# compute_hub.net
KiCad netlist of a schematic drawn in EAGLE
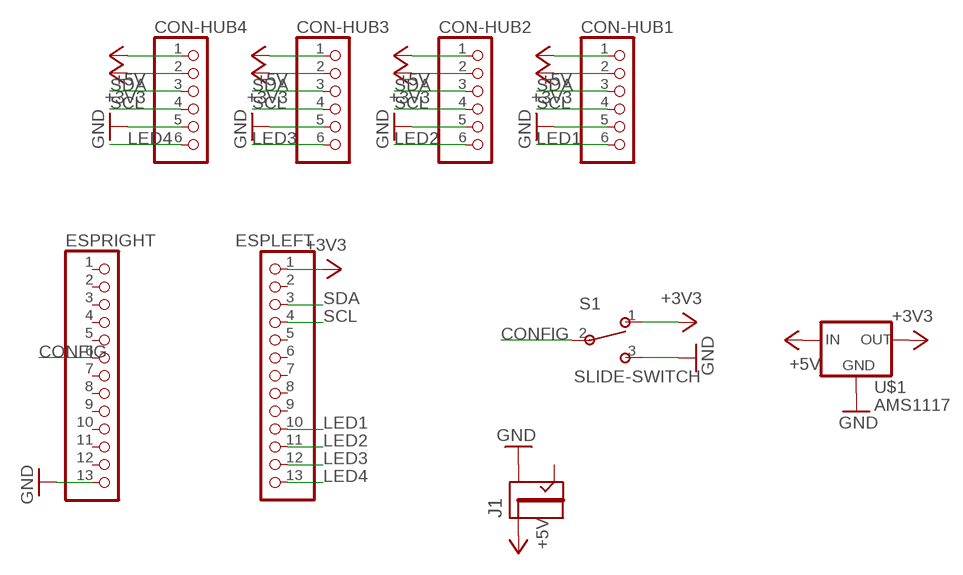
[diagram p0: schematic, sheet 1]

(export (version "E")
  (design (tool "Eeschema 10.0.6"))
  (components
    (comp (ref "CON-HUB1")
      (value "PINHD-1X6")
      (footprint "eagle-import:1X06")
      (libsource (lib "eagle-import") (part "PINHD-1X6"))
    )
    (comp (ref "CON-HUB2")
      (value "PINHD-1X6")
      (footprint "eagle-import:1X06")
      (libsource (lib "eagle-import") (part "PINHD-1X6"))
    )
    (comp (ref "CON-HUB3")
      (value "PINHD-1X6")
      (footprint "eagle-import:1X06")
      (libsource (lib "eagle-import") (part "PINHD-1X6"))
    )
    (comp (ref "CON-HUB4")
      (value "PINHD-1X6")
      (footprint "eagle-import:1X06")
      (libsource (lib "eagle-import") (part "PINHD-1X6"))
    )
    (comp (ref "ESPLEFT")
      (value "PINHD-1X13")
      (footprint "eagle-import:1X13")
      (libsource (lib "eagle-import") (part "PINHD-1X13"))
    )
    (comp (ref "ESPRIGHT")
      (value "PINHD-1X13")
      (footprint "eagle-import:1X13")
      (libsource (lib "eagle-import") (part "PINHD-1X13"))
    )
    (comp (ref "J1")
      (value "JACK2.1MM")
      (footprint "eagle-import:JACK_2.1MM")
      (libsource (lib "eagle-import") (part "JACK2.1MM"))
    )
    (comp (ref "S1")
      (value "SLIDE-SWITCH")
      (footprint "eagle-import:AYZ0102AGRLC")
      (libsource (lib "eagle-import") (part "SLIDE-SWITCH"))
    )
    (comp (ref "U$1")
      (value "AMS1117")
      (footprint "eagle-import:SOT223")
      (libsource (lib "eagle-import") (part "AMS1117"))
    )
  )
  (nets
    (net (code "1") (name "+3V3") (class "Default")
      (node (ref "CON-HUB1") (pin "2") (pinfunction "2_2") (pintype "passive"))
      (node (ref "CON-HUB2") (pin "2") (pinfunction "2_2") (pintype "passive"))
      (node (ref "CON-HUB3") (pin "2") (pinfunction "2_2") (pintype "passive"))
      (node (ref "CON-HUB4") (pin "2") (pinfunction "2_2") (pintype "passive"))
      (node (ref "ESPLEFT") (pin "1") (pinfunction "1_1") (pintype "passive"))
      (node (ref "S1") (pin "1") (pinfunction "1_1") (pintype "bidirectional"))
      (node (ref "U$1") (pin "2") (pinfunction "OUT_2") (pintype "passive"))
    )
    (net (code "2") (name "+5V") (class "Default")
      (node (ref "CON-HUB1") (pin "1") (pinfunction "1_1") (pintype "passive"))
      (node (ref "CON-HUB2") (pin "1") (pinfunction "1_1") (pintype "passive"))
      (node (ref "CON-HUB3") (pin "1") (pinfunction "1_1") (pintype "passive"))
      (node (ref "CON-HUB4") (pin "1") (pinfunction "1_1") (pintype "passive"))
      (node (ref "J1") (pin "PIN") (pinfunction "PIN_PIN") (pintype "bidirectional"))
      (node (ref "U$1") (pin "3") (pinfunction "IN_3") (pintype "input"))
    )
    (net (code "3") (name "/CONFIG") (class "Default")
      (node (ref "ESPRIGHT") (pin "6") (pinfunction "6_6") (pintype "passive"))
      (node (ref "S1") (pin "2") (pinfunction "2_2") (pintype "bidirectional"))
    )
    (net (code "4") (name "/LED1") (class "Default")
      (node (ref "CON-HUB1") (pin "6") (pinfunction "6_6") (pintype "passive"))
      (node (ref "ESPLEFT") (pin "10") (pinfunction "10_10") (pintype "passive"))
    )
    (net (code "5") (name "/LED2") (class "Default")
      (node (ref "CON-HUB2") (pin "6") (pinfunction "6_6") (pintype "passive"))
      (node (ref "ESPLEFT") (pin "11") (pinfunction "11_11") (pintype "passive"))
    )
    (net (code "6") (name "/LED3") (class "Default")
      (node (ref "CON-HUB3") (pin "6") (pinfunction "6_6") (pintype "passive"))
      (node (ref "ESPLEFT") (pin "12") (pinfunction "12_12") (pintype "passive"))
    )
    (net (code "7") (name "/LED4") (class "Default")
      (node (ref "CON-HUB4") (pin "6") (pinfunction "6_6") (pintype "passive"))
      (node (ref "ESPLEFT") (pin "13") (pinfunction "13_13") (pintype "passive"))
    )
    (net (code "8") (name "/SCL") (class "Default")
      (node (ref "CON-HUB1") (pin "4") (pinfunction "4_4") (pintype "passive"))
      (node (ref "CON-HUB2") (pin "4") (pinfunction "4_4") (pintype "passive"))
      (node (ref "CON-HUB3") (pin "4") (pinfunction "4_4") (pintype "passive"))
      (node (ref "CON-HUB4") (pin "4") (pinfunction "4_4") (pintype "passive"))
      (node (ref "ESPLEFT") (pin "4") (pinfunction "4_4") (pintype "passive"))
    )
    (net (code "9") (name "/SDA") (class "Default")
      (node (ref "CON-HUB1") (pin "3") (pinfunction "3_3") (pintype "passive"))
      (node (ref "CON-HUB2") (pin "3") (pinfunction "3_3") (pintype "passive"))
      (node (ref "CON-HUB3") (pin "3") (pinfunction "3_3") (pintype "passive"))
      (node (ref "CON-HUB4") (pin "3") (pinfunction "3_3") (pintype "passive"))
      (node (ref "ESPLEFT") (pin "3") (pinfunction "3_3") (pintype "passive"))
    )
    (net (code "10") (name "GND") (class "Default")
      (node (ref "CON-HUB1") (pin "5") (pinfunction "5_5") (pintype "passive"))
      (node (ref "CON-HUB2") (pin "5") (pinfunction "5_5") (pintype "passive"))
      (node (ref "CON-HUB3") (pin "5") (pinfunction "5_5") (pintype "passive"))
      (node (ref "CON-HUB4") (pin "5") (pinfunction "5_5") (pintype "passive"))
      (node (ref "ESPRIGHT") (pin "13") (pinfunction "13_13") (pintype "passive"))
      (node (ref "J1") (pin "SHUNT") (pinfunction "SHUNT_SHUNT") (pintype "bidirectional"))
      (node (ref "S1") (pin "3") (pinfunction "3_3") (pintype "bidirectional"))
      (node (ref "U$1") (pin "1") (pinfunction "GND_1") (pintype "input"))
    )
    (net (code "11") (name "unconnected-(ESPLEFT-Pad2)") (class "Default")
      (node (ref "ESPLEFT") (pin "2") (pinfunction "2_2") (pintype "passive"))
    )
    (net (code "12") (name "unconnected-(ESPLEFT-Pad5)") (class "Default")
      (node (ref "ESPLEFT") (pin "5") (pinfunction "5_5") (pintype "passive"))
    )
    (net (code "13") (name "unconnected-(ESPLEFT-Pad6)") (class "Default")
      (node (ref "ESPLEFT") (pin "6") (pinfunction "6_6") (pintype "passive"))
    )
    (net (code "14") (name "unconnected-(ESPLEFT-Pad7)") (class "Default")
      (node (ref "ESPLEFT") (pin "7") (pinfunction "7_7") (pintype "passive"))
    )
    (net (code "15") (name "unconnected-(ESPLEFT-Pad8)") (class "Default")
      (node (ref "ESPLEFT") (pin "8") (pinfunction "8_8") (pintype "passive"))
    )
    (net (code "16") (name "unconnected-(ESPLEFT-Pad9)") (class "Default")
      (node (ref "ESPLEFT") (pin "9") (pinfunction "9_9") (pintype "passive"))
    )
    (net (code "17") (name "unconnected-(ESPRIGHT-Pad1)") (class "Default")
      (node (ref "ESPRIGHT") (pin "1") (pinfunction "1_1") (pintype "passive"))
    )
    (net (code "18") (name "unconnected-(ESPRIGHT-Pad2)") (class "Default")
      (node (ref "ESPRIGHT") (pin "2") (pinfunction "2_2") (pintype "passive"))
    )
    (net (code "19") (name "unconnected-(ESPRIGHT-Pad3)") (class "Default")
      (node (ref "ESPRIGHT") (pin "3") (pinfunction "3_3") (pintype "passive"))
    )
    (net (code "20") (name "unconnected-(ESPRIGHT-Pad4)") (class "Default")
      (node (ref "ESPRIGHT") (pin "4") (pinfunction "4_4") (pintype "passive"))
    )
    (net (code "21") (name "unconnected-(ESPRIGHT-Pad5)") (class "Default")
      (node (ref "ESPRIGHT") (pin "5") (pinfunction "5_5") (pintype "passive"))
    )
    (net (code "22") (name "unconnected-(ESPRIGHT-Pad7)") (class "Default")
      (node (ref "ESPRIGHT") (pin "7") (pinfunction "7_7") (pintype "passive"))
    )
    (net (code "23") (name "unconnected-(ESPRIGHT-Pad8)") (class "Default")
      (node (ref "ESPRIGHT") (pin "8") (pinfunction "8_8") (pintype "passive"))
    )
    (net (code "24") (name "unconnected-(ESPRIGHT-Pad9)") (class "Default")
      (node (ref "ESPRIGHT") (pin "9") (pinfunction "9_9") (pintype "passive"))
    )
    (net (code "25") (name "unconnected-(ESPRIGHT-Pad10)") (class "Default")
      (node (ref "ESPRIGHT") (pin "10") (pinfunction "10_10") (pintype "passive"))
    )
    (net (code "26") (name "unconnected-(ESPRIGHT-Pad11)") (class "Default")
      (node (ref "ESPRIGHT") (pin "11") (pinfunction "11_11") (pintype "passive"))
    )
    (net (code "27") (name "unconnected-(ESPRIGHT-Pad12)") (class "Default")
      (node (ref "ESPRIGHT") (pin "12") (pinfunction "12_12") (pintype "passive"))
    )
    (net (code "28") (name "unconnected-(J1-PadCONTACT)") (class "Default")
      (node (ref "J1") (pin "CONTACT") (pinfunction "CONTACT_CONTACT") (pintype "bidirectional"))
    )
  )
)
